# apu-csk-motherboard.net
KiCad netlist of a schematic drawn in EAGLE
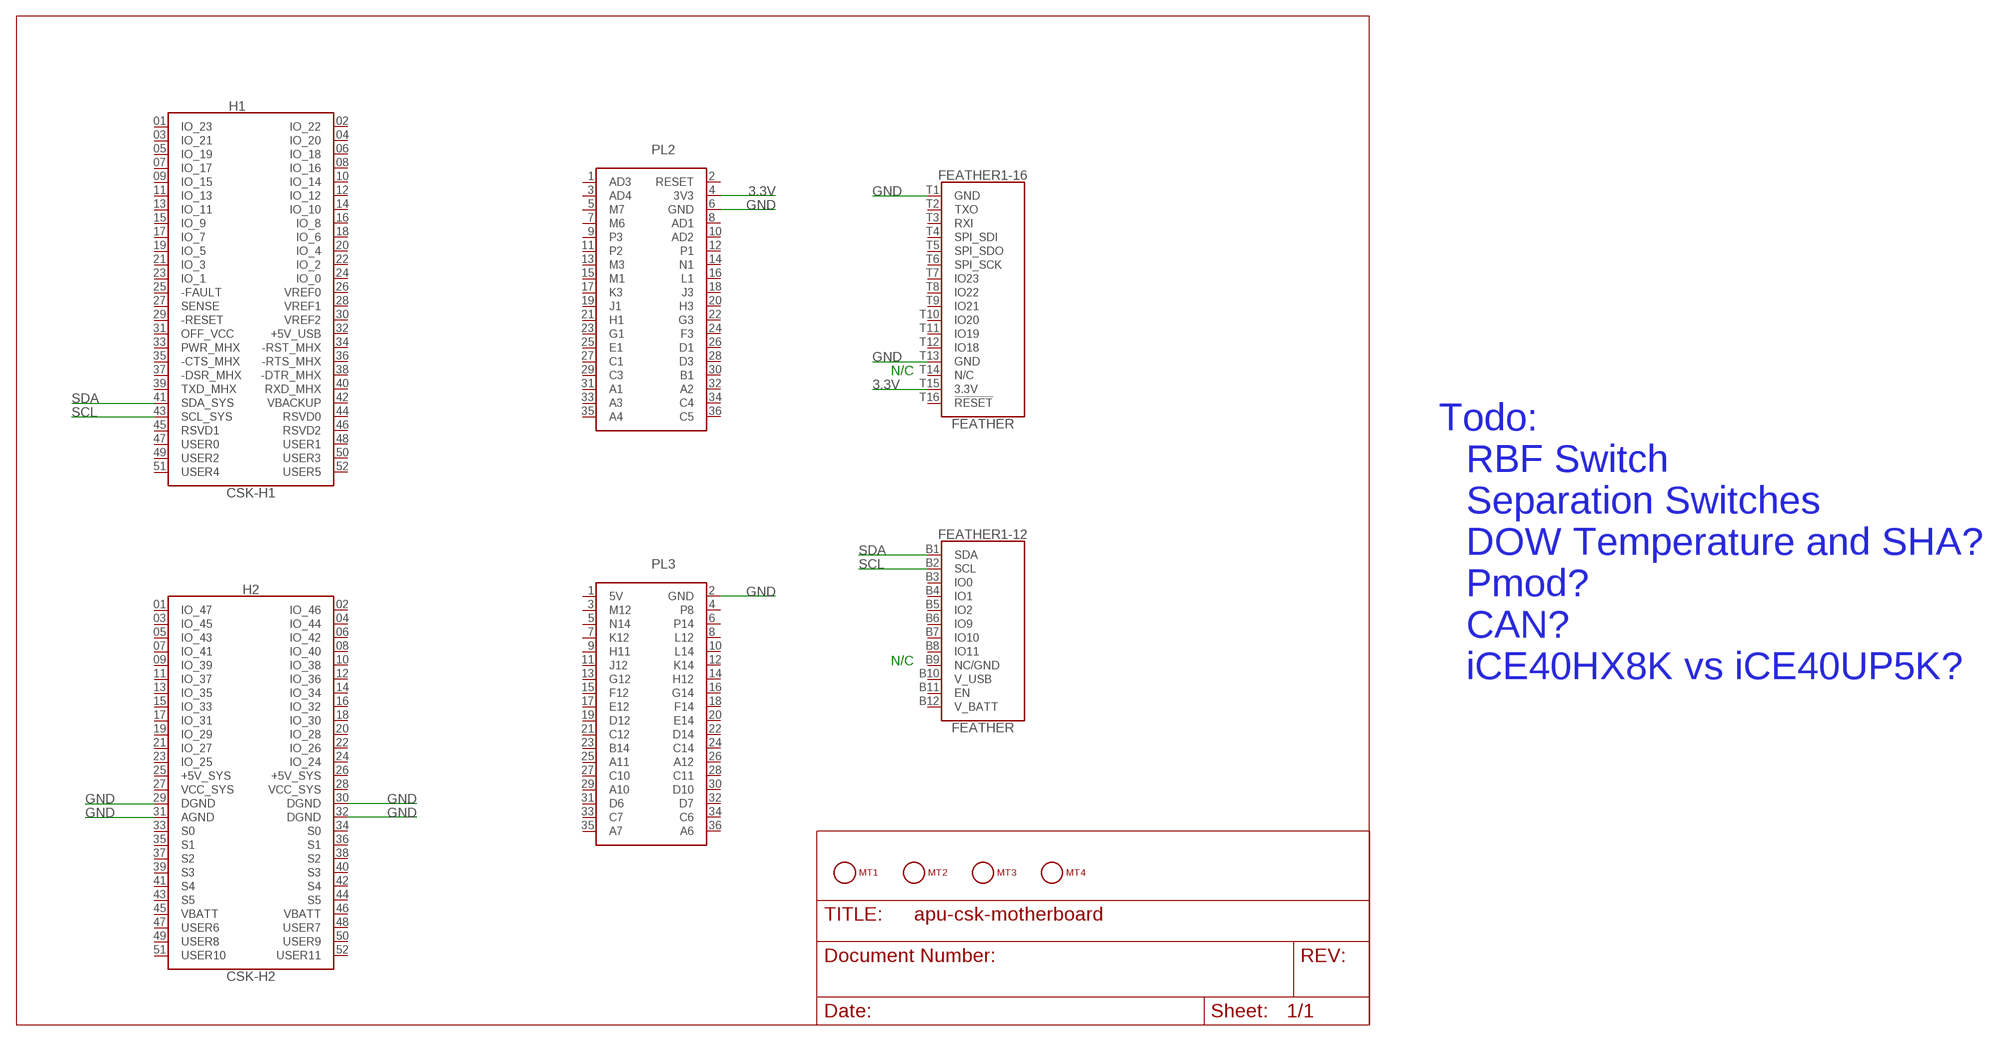
[diagram p0: schematic, sheet 1]

(export (version "E")
  (design (tool "Eeschema 10.0.6"))
  (components
    (comp (ref "FEATHER1")
      (value "FEATHER")
      (footprint "eagle-import:FEATHER")
      (libsource (lib "eagle-import") (part "FEATHER"))
    )
    (comp (ref "H1")
      (value "CSK-H1")
      (footprint "eagle-import:SAMTEC_ESQ-126-37-G-D--NUMBERED-FOR-CUBESAT-BUS")
      (libsource (lib "eagle-import") (part "CSK-H1"))
    )
    (comp (ref "H2")
      (value "CSK-H2")
      (footprint "eagle-import:SAMTEC_ESQ-126-37-G-D--NUMBERED-FOR-CUBESAT-BUS")
      (libsource (lib "eagle-import") (part "CSK-H2"))
    )
    (comp (ref "MT1")
      (value "MOUNTING_HOLE-125_250_ROUND")
      (footprint "eagle-import:MT_125_250")
      (libsource (lib "eagle-import") (part "MOUNTING_HOLE-125_250_ROUND"))
    )
    (comp (ref "MT2")
      (value "MOUNTING_HOLE-125_250_ROUND")
      (footprint "eagle-import:MT_125_250")
      (libsource (lib "eagle-import") (part "MOUNTING_HOLE-125_250_ROUND"))
    )
    (comp (ref "MT3")
      (value "MOUNTING_HOLE-125_250_ROUND")
      (footprint "eagle-import:MT_125_250")
      (libsource (lib "eagle-import") (part "MOUNTING_HOLE-125_250_ROUND"))
    )
    (comp (ref "MT4")
      (value "MOUNTING_HOLE-125_250_ROUND")
      (footprint "eagle-import:MT_125_250")
      (libsource (lib "eagle-import") (part "MOUNTING_HOLE-125_250_ROUND"))
    )
    (comp (ref "PL2")
      (value "ICEWERX-PL2")
      (footprint "eagle-import:TE_4-1734506-1")
      (libsource (lib "eagle-import") (part "ICEWERX-PL2"))
    )
    (comp (ref "PL3")
      (value "ICEWERX-PL3")
      (footprint "eagle-import:TE_4-1734506-1")
      (libsource (lib "eagle-import") (part "ICEWERX-PL3"))
    )
  )
  (nets
    (net (code "1") (name "/3.3V") (class "Default")
      (node (ref "FEATHER1") (pin "T15") (pinfunction "3.3V_T15") (pintype "bidirectional"))
      (node (ref "PL2") (pin "4") (pinfunction "3V3_4") (pintype "bidirectional"))
    )
    (net (code "2") (name "/GND") (class "Default")
      (node (ref "FEATHER1") (pin "T1") (pinfunction "GND_T1") (pintype "bidirectional"))
      (node (ref "FEATHER1") (pin "T13") (pinfunction "GND_T13") (pintype "bidirectional"))
      (node (ref "H2") (pin "29") (pinfunction "DGND_29") (pintype "bidirectional"))
      (node (ref "H2") (pin "30") (pinfunction "DGND_30") (pintype "bidirectional"))
      (node (ref "H2") (pin "31") (pinfunction "AGND_31") (pintype "bidirectional"))
      (node (ref "H2") (pin "32") (pinfunction "DGND_32") (pintype "bidirectional"))
      (node (ref "PL2") (pin "6") (pinfunction "GND_6") (pintype "bidirectional"))
      (node (ref "PL3") (pin "2") (pinfunction "GND_2") (pintype "bidirectional"))
    )
    (net (code "3") (name "/SCL") (class "Default")
      (node (ref "FEATHER1") (pin "B2") (pinfunction "SCL_B2") (pintype "bidirectional"))
      (node (ref "H1") (pin "43") (pinfunction "SCL_SYS_43") (pintype "bidirectional"))
    )
    (net (code "4") (name "/SDA") (class "Default")
      (node (ref "FEATHER1") (pin "B1") (pinfunction "SDA_B1") (pintype "bidirectional"))
      (node (ref "H1") (pin "41") (pinfunction "SDA_SYS_41") (pintype "bidirectional"))
    )
    (net (code "5") (name "unconnected-(FEATHER1A-EN-PadB11)") (class "Default")
      (node (ref "FEATHER1") (pin "B11") (pinfunction "EN_B11") (pintype "bidirectional"))
    )
    (net (code "6") (name "unconnected-(FEATHER1A-IO0-PadB3)") (class "Default")
      (node (ref "FEATHER1") (pin "B3") (pinfunction "IO0_B3") (pintype "bidirectional"))
    )
    (net (code "7") (name "unconnected-(FEATHER1A-IO1-PadB4)") (class "Default")
      (node (ref "FEATHER1") (pin "B4") (pinfunction "IO1_B4") (pintype "bidirectional"))
    )
    (net (code "8") (name "unconnected-(FEATHER1A-IO2-PadB5)") (class "Default")
      (node (ref "FEATHER1") (pin "B5") (pinfunction "IO2_B5") (pintype "bidirectional"))
    )
    (net (code "9") (name "unconnected-(FEATHER1A-IO9-PadB6)") (class "Default")
      (node (ref "FEATHER1") (pin "B6") (pinfunction "IO9_B6") (pintype "bidirectional"))
    )
    (net (code "10") (name "unconnected-(FEATHER1A-IO10-PadB7)") (class "Default")
      (node (ref "FEATHER1") (pin "B7") (pinfunction "IO10_B7") (pintype "bidirectional"))
    )
    (net (code "11") (name "unconnected-(FEATHER1A-IO11-PadB8)") (class "Default")
      (node (ref "FEATHER1") (pin "B8") (pinfunction "IO11_B8") (pintype "bidirectional"))
    )
    (net (code "12") (name "unconnected-(FEATHER1A-NC{slash}GND-PadB9)") (class "Default")
      (node (ref "FEATHER1") (pin "B9") (pinfunction "NC/GND_B9") (pintype "bidirectional"))
    )
    (net (code "13") (name "unconnected-(FEATHER1A-V_BATT-PadB12)") (class "Default")
      (node (ref "FEATHER1") (pin "B12") (pinfunction "V_BATT_B12") (pintype "bidirectional"))
    )
    (net (code "14") (name "unconnected-(FEATHER1A-V_USB-PadB10)") (class "Default")
      (node (ref "FEATHER1") (pin "B10") (pinfunction "V_USB_B10") (pintype "bidirectional"))
    )
    (net (code "15") (name "unconnected-(FEATHER1B-IO18-PadT12)") (class "Default")
      (node (ref "FEATHER1") (pin "T12") (pinfunction "IO18_T12") (pintype "bidirectional"))
    )
    (net (code "16") (name "unconnected-(FEATHER1B-IO19-PadT11)") (class "Default")
      (node (ref "FEATHER1") (pin "T11") (pinfunction "IO19_T11") (pintype "bidirectional"))
    )
    (net (code "17") (name "unconnected-(FEATHER1B-IO20-PadT10)") (class "Default")
      (node (ref "FEATHER1") (pin "T10") (pinfunction "IO20_T10") (pintype "bidirectional"))
    )
    (net (code "18") (name "unconnected-(FEATHER1B-IO21-PadT9)") (class "Default")
      (node (ref "FEATHER1") (pin "T9") (pinfunction "IO21_T9") (pintype "bidirectional"))
    )
    (net (code "19") (name "unconnected-(FEATHER1B-IO22-PadT8)") (class "Default")
      (node (ref "FEATHER1") (pin "T8") (pinfunction "IO22_T8") (pintype "bidirectional"))
    )
    (net (code "20") (name "unconnected-(FEATHER1B-IO23-PadT7)") (class "Default")
      (node (ref "FEATHER1") (pin "T7") (pinfunction "IO23_T7") (pintype "bidirectional"))
    )
    (net (code "21") (name "unconnected-(FEATHER1B-N{slash}C-PadT14)") (class "Default")
      (node (ref "FEATHER1") (pin "T14") (pinfunction "N/C_T14") (pintype "bidirectional"))
    )
    (net (code "22") (name "unconnected-(FEATHER1B-RXI-PadT3)") (class "Default")
      (node (ref "FEATHER1") (pin "T3") (pinfunction "RXI_T3") (pintype "bidirectional"))
    )
    (net (code "23") (name "unconnected-(FEATHER1B-SPI_SCK-PadT6)") (class "Default")
      (node (ref "FEATHER1") (pin "T6") (pinfunction "SPI_SCK_T6") (pintype "bidirectional"))
    )
    (net (code "24") (name "unconnected-(FEATHER1B-SPI_SDI-PadT4)") (class "Default")
      (node (ref "FEATHER1") (pin "T4") (pinfunction "SPI_SDI_T4") (pintype "bidirectional"))
    )
    (net (code "25") (name "unconnected-(FEATHER1B-SPI_SDO-PadT5)") (class "Default")
      (node (ref "FEATHER1") (pin "T5") (pinfunction "SPI_SDO_T5") (pintype "bidirectional"))
    )
    (net (code "26") (name "unconnected-(FEATHER1B-TXO-PadT2)") (class "Default")
      (node (ref "FEATHER1") (pin "T2") (pinfunction "TXO_T2") (pintype "bidirectional"))
    )
    (net (code "27") (name "unconnected-(FEATHER1B-~{RESET}-PadT16)") (class "Default")
      (node (ref "FEATHER1") (pin "T16") (pinfunction "~{RESET}_T16") (pintype "bidirectional"))
    )
    (net (code "28") (name "unconnected-(H1-+5V_USB-Pad32)") (class "Default")
      (node (ref "H1") (pin "32") (pinfunction "+5V_USB_32") (pintype "bidirectional"))
    )
    (net (code "29") (name "unconnected-(H1--CTS_MHX-Pad35)") (class "Default")
      (node (ref "H1") (pin "35") (pinfunction "-CTS_MHX_35") (pintype "bidirectional"))
    )
    (net (code "30") (name "unconnected-(H1--DSR_MHX-Pad37)") (class "Default")
      (node (ref "H1") (pin "37") (pinfunction "-DSR_MHX_37") (pintype "bidirectional"))
    )
    (net (code "31") (name "unconnected-(H1--DTR_MHX-Pad38)") (class "Default")
      (node (ref "H1") (pin "38") (pinfunction "-DTR_MHX_38") (pintype "bidirectional"))
    )
    (net (code "32") (name "unconnected-(H1--FAULT-Pad25)") (class "Default")
      (node (ref "H1") (pin "25") (pinfunction "-FAULT_25") (pintype "bidirectional"))
    )
    (net (code "33") (name "unconnected-(H1--RESET-Pad29)") (class "Default")
      (node (ref "H1") (pin "29") (pinfunction "-RESET_29") (pintype "bidirectional"))
    )
    (net (code "34") (name "unconnected-(H1--RST_MHX-Pad34)") (class "Default")
      (node (ref "H1") (pin "34") (pinfunction "-RST_MHX_34") (pintype "bidirectional"))
    )
    (net (code "35") (name "unconnected-(H1--RTS_MHX-Pad36)") (class "Default")
      (node (ref "H1") (pin "36") (pinfunction "-RTS_MHX_36") (pintype "bidirectional"))
    )
    (net (code "36") (name "unconnected-(H1-IO_0-Pad24)") (class "Default")
      (node (ref "H1") (pin "24") (pinfunction "IO_0_24") (pintype "bidirectional"))
    )
    (net (code "37") (name "unconnected-(H1-IO_1-Pad23)") (class "Default")
      (node (ref "H1") (pin "23") (pinfunction "IO_1_23") (pintype "bidirectional"))
    )
    (net (code "38") (name "unconnected-(H1-IO_2-Pad22)") (class "Default")
      (node (ref "H1") (pin "22") (pinfunction "IO_2_22") (pintype "bidirectional"))
    )
    (net (code "39") (name "unconnected-(H1-IO_3-Pad21)") (class "Default")
      (node (ref "H1") (pin "21") (pinfunction "IO_3_21") (pintype "bidirectional"))
    )
    (net (code "40") (name "unconnected-(H1-IO_4-Pad20)") (class "Default")
      (node (ref "H1") (pin "20") (pinfunction "IO_4_20") (pintype "bidirectional"))
    )
    (net (code "41") (name "unconnected-(H1-IO_5-Pad19)") (class "Default")
      (node (ref "H1") (pin "19") (pinfunction "IO_5_19") (pintype "bidirectional"))
    )
    (net (code "42") (name "unconnected-(H1-IO_6-Pad18)") (class "Default")
      (node (ref "H1") (pin "18") (pinfunction "IO_6_18") (pintype "bidirectional"))
    )
    (net (code "43") (name "unconnected-(H1-IO_7-Pad17)") (class "Default")
      (node (ref "H1") (pin "17") (pinfunction "IO_7_17") (pintype "bidirectional"))
    )
    (net (code "44") (name "unconnected-(H1-IO_8-Pad16)") (class "Default")
      (node (ref "H1") (pin "16") (pinfunction "IO_8_16") (pintype "bidirectional"))
    )
    (net (code "45") (name "unconnected-(H1-IO_9-Pad15)") (class "Default")
      (node (ref "H1") (pin "15") (pinfunction "IO_9_15") (pintype "bidirectional"))
    )
    (net (code "46") (name "unconnected-(H1-IO_10-Pad14)") (class "Default")
      (node (ref "H1") (pin "14") (pinfunction "IO_10_14") (pintype "bidirectional"))
    )
    (net (code "47") (name "unconnected-(H1-IO_11-Pad13)") (class "Default")
      (node (ref "H1") (pin "13") (pinfunction "IO_11_13") (pintype "bidirectional"))
    )
    (net (code "48") (name "unconnected-(H1-IO_12-Pad12)") (class "Default")
      (node (ref "H1") (pin "12") (pinfunction "IO_12_12") (pintype "bidirectional"))
    )
    (net (code "49") (name "unconnected-(H1-IO_13-Pad11)") (class "Default")
      (node (ref "H1") (pin "11") (pinfunction "IO_13_11") (pintype "bidirectional"))
    )
    (net (code "50") (name "unconnected-(H1-IO_14-Pad10)") (class "Default")
      (node (ref "H1") (pin "10") (pinfunction "IO_14_10") (pintype "bidirectional"))
    )
    (net (code "51") (name "unconnected-(H1-IO_15-Pad09)") (class "Default")
      (node (ref "H1") (pin "09") (pinfunction "IO_15_09") (pintype "bidirectional"))
    )
    (net (code "52") (name "unconnected-(H1-IO_16-Pad08)") (class "Default")
      (node (ref "H1") (pin "08") (pinfunction "IO_16_08") (pintype "bidirectional"))
    )
    (net (code "53") (name "unconnected-(H1-IO_17-Pad07)") (class "Default")
      (node (ref "H1") (pin "07") (pinfunction "IO_17_07") (pintype "bidirectional"))
    )
    (net (code "54") (name "unconnected-(H1-IO_18-Pad06)") (class "Default")
      (node (ref "H1") (pin "06") (pinfunction "IO_18_06") (pintype "bidirectional"))
    )
    (net (code "55") (name "unconnected-(H1-IO_19-Pad05)") (class "Default")
      (node (ref "H1") (pin "05") (pinfunction "IO_19_05") (pintype "bidirectional"))
    )
    (net (code "56") (name "unconnected-(H1-IO_20-Pad04)") (class "Default")
      (node (ref "H1") (pin "04") (pinfunction "IO_20_04") (pintype "bidirectional"))
    )
    (net (code "57") (name "unconnected-(H1-IO_21-Pad03)") (class "Default")
      (node (ref "H1") (pin "03") (pinfunction "IO_21_03") (pintype "bidirectional"))
    )
    (net (code "58") (name "unconnected-(H1-IO_22-Pad02)") (class "Default")
      (node (ref "H1") (pin "02") (pinfunction "IO_22_02") (pintype "bidirectional"))
    )
    (net (code "59") (name "unconnected-(H1-IO_23-Pad01)") (class "Default")
      (node (ref "H1") (pin "01") (pinfunction "IO_23_01") (pintype "bidirectional"))
    )
    (net (code "60") (name "unconnected-(H1-OFF_VCC-Pad31)") (class "Default")
      (node (ref "H1") (pin "31") (pinfunction "OFF_VCC_31") (pintype "bidirectional"))
    )
    (net (code "61") (name "unconnected-(H1-PWR_MHX-Pad33)") (class "Default")
      (node (ref "H1") (pin "33") (pinfunction "PWR_MHX_33") (pintype "bidirectional"))
    )
    (net (code "62") (name "unconnected-(H1-RSVD0-Pad44)") (class "Default")
      (node (ref "H1") (pin "44") (pinfunction "RSVD0_44") (pintype "bidirectional"))
    )
    (net (code "63") (name "unconnected-(H1-RSVD1-Pad45)") (class "Default")
      (node (ref "H1") (pin "45") (pinfunction "RSVD1_45") (pintype "bidirectional"))
    )
    (net (code "64") (name "unconnected-(H1-RSVD2-Pad46)") (class "Default")
      (node (ref "H1") (pin "46") (pinfunction "RSVD2_46") (pintype "bidirectional"))
    )
    (net (code "65") (name "unconnected-(H1-RXD_MHX-Pad40)") (class "Default")
      (node (ref "H1") (pin "40") (pinfunction "RXD_MHX_40") (pintype "bidirectional"))
    )
    (net (code "66") (name "unconnected-(H1-SENSE-Pad27)") (class "Default")
      (node (ref "H1") (pin "27") (pinfunction "SENSE_27") (pintype "bidirectional"))
    )
    (net (code "67") (name "unconnected-(H1-TXD_MHX-Pad39)") (class "Default")
      (node (ref "H1") (pin "39") (pinfunction "TXD_MHX_39") (pintype "bidirectional"))
    )
    (net (code "68") (name "unconnected-(H1-USER0-Pad47)") (class "Default")
      (node (ref "H1") (pin "47") (pinfunction "USER0_47") (pintype "bidirectional"))
    )
    (net (code "69") (name "unconnected-(H1-USER1-Pad48)") (class "Default")
      (node (ref "H1") (pin "48") (pinfunction "USER1_48") (pintype "bidirectional"))
    )
    (net (code "70") (name "unconnected-(H1-USER2-Pad49)") (class "Default")
      (node (ref "H1") (pin "49") (pinfunction "USER2_49") (pintype "bidirectional"))
    )
    (net (code "71") (name "unconnected-(H1-USER3-Pad50)") (class "Default")
      (node (ref "H1") (pin "50") (pinfunction "USER3_50") (pintype "bidirectional"))
    )
    (net (code "72") (name "unconnected-(H1-USER4-Pad51)") (class "Default")
      (node (ref "H1") (pin "51") (pinfunction "USER4_51") (pintype "bidirectional"))
    )
    (net (code "73") (name "unconnected-(H1-USER5-Pad52)") (class "Default")
      (node (ref "H1") (pin "52") (pinfunction "USER5_52") (pintype "bidirectional"))
    )
    (net (code "74") (name "unconnected-(H1-VBACKUP-Pad42)") (class "Default")
      (node (ref "H1") (pin "42") (pinfunction "VBACKUP_42") (pintype "bidirectional"))
    )
    (net (code "75") (name "unconnected-(H1-VREF0-Pad26)") (class "Default")
      (node (ref "H1") (pin "26") (pinfunction "VREF0_26") (pintype "bidirectional"))
    )
    (net (code "76") (name "unconnected-(H1-VREF1-Pad28)") (class "Default")
      (node (ref "H1") (pin "28") (pinfunction "VREF1_28") (pintype "bidirectional"))
    )
    (net (code "77") (name "unconnected-(H1-VREF2-Pad30)") (class "Default")
      (node (ref "H1") (pin "30") (pinfunction "VREF2_30") (pintype "bidirectional"))
    )
    (net (code "78") (name "unconnected-(H2-+5V_SYS-Pad25)") (class "Default")
      (node (ref "H2") (pin "25") (pinfunction "+5V_SYS_25") (pintype "bidirectional"))
    )
    (net (code "79") (name "unconnected-(H2-+5V_SYS-Pad26)") (class "Default")
      (node (ref "H2") (pin "26") (pinfunction "+5V_SYS_26") (pintype "bidirectional"))
    )
    (net (code "80") (name "unconnected-(H2-IO_24-Pad24)") (class "Default")
      (node (ref "H2") (pin "24") (pinfunction "IO_24_24") (pintype "bidirectional"))
    )
    (net (code "81") (name "unconnected-(H2-IO_25-Pad23)") (class "Default")
      (node (ref "H2") (pin "23") (pinfunction "IO_25_23") (pintype "bidirectional"))
    )
    (net (code "82") (name "unconnected-(H2-IO_26-Pad22)") (class "Default")
      (node (ref "H2") (pin "22") (pinfunction "IO_26_22") (pintype "bidirectional"))
    )
    (net (code "83") (name "unconnected-(H2-IO_27-Pad21)") (class "Default")
      (node (ref "H2") (pin "21") (pinfunction "IO_27_21") (pintype "bidirectional"))
    )
    (net (code "84") (name "unconnected-(H2-IO_28-Pad20)") (class "Default")
      (node (ref "H2") (pin "20") (pinfunction "IO_28_20") (pintype "bidirectional"))
    )
    (net (code "85") (name "unconnected-(H2-IO_29-Pad19)") (class "Default")
      (node (ref "H2") (pin "19") (pinfunction "IO_29_19") (pintype "bidirectional"))
    )
    (net (code "86") (name "unconnected-(H2-IO_30-Pad18)") (class "Default")
      (node (ref "H2") (pin "18") (pinfunction "IO_30_18") (pintype "bidirectional"))
    )
    (net (code "87") (name "unconnected-(H2-IO_31-Pad17)") (class "Default")
      (node (ref "H2") (pin "17") (pinfunction "IO_31_17") (pintype "bidirectional"))
    )
    (net (code "88") (name "unconnected-(H2-IO_32-Pad16)") (class "Default")
      (node (ref "H2") (pin "16") (pinfunction "IO_32_16") (pintype "bidirectional"))
    )
    (net (code "89") (name "unconnected-(H2-IO_33-Pad15)") (class "Default")
      (node (ref "H2") (pin "15") (pinfunction "IO_33_15") (pintype "bidirectional"))
    )
    (net (code "90") (name "unconnected-(H2-IO_34-Pad14)") (class "Default")
      (node (ref "H2") (pin "14") (pinfunction "IO_34_14") (pintype "bidirectional"))
    )
    (net (code "91") (name "unconnected-(H2-IO_35-Pad13)") (class "Default")
      (node (ref "H2") (pin "13") (pinfunction "IO_35_13") (pintype "bidirectional"))
    )
    (net (code "92") (name "unconnected-(H2-IO_36-Pad12)") (class "Default")
      (node (ref "H2") (pin "12") (pinfunction "IO_36_12") (pintype "bidirectional"))
    )
    (net (code "93") (name "unconnected-(H2-IO_37-Pad11)") (class "Default")
      (node (ref "H2") (pin "11") (pinfunction "IO_37_11") (pintype "bidirectional"))
    )
    (net (code "94") (name "unconnected-(H2-IO_38-Pad10)") (class "Default")
      (node (ref "H2") (pin "10") (pinfunction "IO_38_10") (pintype "bidirectional"))
    )
    (net (code "95") (name "unconnected-(H2-IO_39-Pad09)") (class "Default")
      (node (ref "H2") (pin "09") (pinfunction "IO_39_09") (pintype "bidirectional"))
    )
    (net (code "96") (name "unconnected-(H2-IO_40-Pad08)") (class "Default")
      (node (ref "H2") (pin "08") (pinfunction "IO_40_08") (pintype "bidirectional"))
    )
    (net (code "97") (name "unconnected-(H2-IO_41-Pad07)") (class "Default")
      (node (ref "H2") (pin "07") (pinfunction "IO_41_07") (pintype "bidirectional"))
    )
    (net (code "98") (name "unconnected-(H2-IO_42-Pad06)") (class "Default")
      (node (ref "H2") (pin "06") (pinfunction "IO_42_06") (pintype "bidirectional"))
    )
    (net (code "99") (name "unconnected-(H2-IO_43-Pad05)") (class "Default")
      (node (ref "H2") (pin "05") (pinfunction "IO_43_05") (pintype "bidirectional"))
    )
    (net (code "100") (name "unconnected-(H2-IO_44-Pad04)") (class "Default")
      (node (ref "H2") (pin "04") (pinfunction "IO_44_04") (pintype "bidirectional"))
    )
    (net (code "101") (name "unconnected-(H2-IO_45-Pad03)") (class "Default")
      (node (ref "H2") (pin "03") (pinfunction "IO_45_03") (pintype "bidirectional"))
    )
    (net (code "102") (name "unconnected-(H2-IO_46-Pad02)") (class "Default")
      (node (ref "H2") (pin "02") (pinfunction "IO_46_02") (pintype "bidirectional"))
    )
    (net (code "103") (name "unconnected-(H2-IO_47-Pad01)") (class "Default")
      (node (ref "H2") (pin "01") (pinfunction "IO_47_01") (pintype "bidirectional"))
    )
    (net (code "104") (name "unconnected-(H2-S0-Pad33)") (class "Default")
      (node (ref "H2") (pin "33") (pinfunction "S0_33") (pintype "bidirectional"))
    )
    (net (code "105") (name "unconnected-(H2-S0-Pad34)") (class "Default")
      (node (ref "H2") (pin "34") (pinfunction "S0_34") (pintype "bidirectional"))
    )
    (net (code "106") (name "unconnected-(H2-S1-Pad35)") (class "Default")
      (node (ref "H2") (pin "35") (pinfunction "S1_35") (pintype "bidirectional"))
    )
    (net (code "107") (name "unconnected-(H2-S1-Pad36)") (class "Default")
      (node (ref "H2") (pin "36") (pinfunction "S1_36") (pintype "bidirectional"))
    )
    (net (code "108") (name "unconnected-(H2-S2-Pad37)") (class "Default")
      (node (ref "H2") (pin "37") (pinfunction "S2_37") (pintype "bidirectional"))
    )
    (net (code "109") (name "unconnected-(H2-S2-Pad38)") (class "Default")
      (node (ref "H2") (pin "38") (pinfunction "S2_38") (pintype "bidirectional"))
    )
    (net (code "110") (name "unconnected-(H2-S3-Pad39)") (class "Default")
      (node (ref "H2") (pin "39") (pinfunction "S3_39") (pintype "bidirectional"))
    )
    (net (code "111") (name "unconnected-(H2-S3-Pad40)") (class "Default")
      (node (ref "H2") (pin "40") (pinfunction "S3_40") (pintype "bidirectional"))
    )
    (net (code "112") (name "unconnected-(H2-S4-Pad41)") (class "Default")
      (node (ref "H2") (pin "41") (pinfunction "S4_41") (pintype "bidirectional"))
    )
    (net (code "113") (name "unconnected-(H2-S4-Pad42)") (class "Default")
      (node (ref "H2") (pin "42") (pinfunction "S4_42") (pintype "bidirectional"))
    )
    (net (code "114") (name "unconnected-(H2-S5-Pad43)") (class "Default")
      (node (ref "H2") (pin "43") (pinfunction "S5_43") (pintype "bidirectional"))
    )
    (net (code "115") (name "unconnected-(H2-S5-Pad44)") (class "Default")
      (node (ref "H2") (pin "44") (pinfunction "S5_44") (pintype "bidirectional"))
    )
    (net (code "116") (name "unconnected-(H2-USER6-Pad47)") (class "Default")
      (node (ref "H2") (pin "47") (pinfunction "USER6_47") (pintype "bidirectional"))
    )
    (net (code "117") (name "unconnected-(H2-USER7-Pad48)") (class "Default")
      (node (ref "H2") (pin "48") (pinfunction "USER7_48") (pintype "bidirectional"))
    )
    (net (code "118") (name "unconnected-(H2-USER8-Pad49)") (class "Default")
      (node (ref "H2") (pin "49") (pinfunction "USER8_49") (pintype "bidirectional"))
    )
    (net (code "119") (name "unconnected-(H2-USER9-Pad50)") (class "Default")
      (node (ref "H2") (pin "50") (pinfunction "USER9_50") (pintype "bidirectional"))
    )
    (net (code "120") (name "unconnected-(H2-USER10-Pad51)") (class "Default")
      (node (ref "H2") (pin "51") (pinfunction "USER10_51") (pintype "bidirectional"))
    )
    (net (code "121") (name "unconnected-(H2-USER11-Pad52)") (class "Default")
      (node (ref "H2") (pin "52") (pinfunction "USER11_52") (pintype "bidirectional"))
    )
    (net (code "122") (name "unconnected-(H2-VBATT-Pad45)") (class "Default")
      (node (ref "H2") (pin "45") (pinfunction "VBATT_45") (pintype "bidirectional"))
    )
    (net (code "123") (name "unconnected-(H2-VBATT-Pad46)") (class "Default")
      (node (ref "H2") (pin "46") (pinfunction "VBATT_46") (pintype "bidirectional"))
    )
    (net (code "124") (name "unconnected-(H2-VCC_SYS-Pad27)") (class "Default")
      (node (ref "H2") (pin "27") (pinfunction "VCC_SYS_27") (pintype "bidirectional"))
    )
    (net (code "125") (name "unconnected-(H2-VCC_SYS-Pad28)") (class "Default")
      (node (ref "H2") (pin "28") (pinfunction "VCC_SYS_28") (pintype "bidirectional"))
    )
    (net (code "126") (name "unconnected-(MT1-P$1-Pad1)") (class "Default")
      (node (ref "MT1") (pin "1") (pinfunction "P$1_1") (pintype "bidirectional"))
    )
    (net (code "127") (name "unconnected-(MT2-P$1-Pad1)") (class "Default")
      (node (ref "MT2") (pin "1") (pinfunction "P$1_1") (pintype "bidirectional"))
    )
    (net (code "128") (name "unconnected-(MT3-P$1-Pad1)") (class "Default")
      (node (ref "MT3") (pin "1") (pinfunction "P$1_1") (pintype "bidirectional"))
    )
    (net (code "129") (name "unconnected-(MT4-P$1-Pad1)") (class "Default")
      (node (ref "MT4") (pin "1") (pinfunction "P$1_1") (pintype "bidirectional"))
    )
    (net (code "130") (name "unconnected-(PL2-A1-Pad31)") (class "Default")
      (node (ref "PL2") (pin "31") (pinfunction "A1_31") (pintype "bidirectional"))
    )
    (net (code "131") (name "unconnected-(PL2-A2-Pad32)") (class "Default")
      (node (ref "PL2") (pin "32") (pinfunction "A2_32") (pintype "bidirectional"))
    )
    (net (code "132") (name "unconnected-(PL2-A3-Pad33)") (class "Default")
      (node (ref "PL2") (pin "33") (pinfunction "A3_33") (pintype "bidirectional"))
    )
    (net (code "133") (name "unconnected-(PL2-A4-Pad35)") (class "Default")
      (node (ref "PL2") (pin "35") (pinfunction "A4_35") (pintype "bidirectional"))
    )
    (net (code "134") (name "unconnected-(PL2-AD1-Pad8)") (class "Default")
      (node (ref "PL2") (pin "8") (pinfunction "AD1_8") (pintype "bidirectional"))
    )
    (net (code "135") (name "unconnected-(PL2-AD2-Pad10)") (class "Default")
      (node (ref "PL2") (pin "10") (pinfunction "AD2_10") (pintype "bidirectional"))
    )
    (net (code "136") (name "unconnected-(PL2-AD3-Pad1)") (class "Default")
      (node (ref "PL2") (pin "1") (pinfunction "AD3_1") (pintype "bidirectional"))
    )
    (net (code "137") (name "unconnected-(PL2-AD4-Pad3)") (class "Default")
      (node (ref "PL2") (pin "3") (pinfunction "AD4_3") (pintype "bidirectional"))
    )
    (net (code "138") (name "unconnected-(PL2-B1-Pad30)") (class "Default")
      (node (ref "PL2") (pin "30") (pinfunction "B1_30") (pintype "bidirectional"))
    )
    (net (code "139") (name "unconnected-(PL2-C1-Pad27)") (class "Default")
      (node (ref "PL2") (pin "27") (pinfunction "C1_27") (pintype "bidirectional"))
    )
    (net (code "140") (name "unconnected-(PL2-C3-Pad29)") (class "Default")
      (node (ref "PL2") (pin "29") (pinfunction "C3_29") (pintype "bidirectional"))
    )
    (net (code "141") (name "unconnected-(PL2-C4-Pad34)") (class "Default")
      (node (ref "PL2") (pin "34") (pinfunction "C4_34") (pintype "bidirectional"))
    )
    (net (code "142") (name "unconnected-(PL2-C5-Pad36)") (class "Default")
      (node (ref "PL2") (pin "36") (pinfunction "C5_36") (pintype "bidirectional"))
    )
    (net (code "143") (name "unconnected-(PL2-D1-Pad26)") (class "Default")
      (node (ref "PL2") (pin "26") (pinfunction "D1_26") (pintype "bidirectional"))
    )
    (net (code "144") (name "unconnected-(PL2-D3-Pad28)") (class "Default")
      (node (ref "PL2") (pin "28") (pinfunction "D3_28") (pintype "bidirectional"))
    )
    (net (code "145") (name "unconnected-(PL2-E1-Pad25)") (class "Default")
      (node (ref "PL2") (pin "25") (pinfunction "E1_25") (pintype "bidirectional"))
    )
    (net (code "146") (name "unconnected-(PL2-F3-Pad24)") (class "Default")
      (node (ref "PL2") (pin "24") (pinfunction "F3_24") (pintype "bidirectional"))
    )
    (net (code "147") (name "unconnected-(PL2-G1-Pad23)") (class "Default")
      (node (ref "PL2") (pin "23") (pinfunction "G1_23") (pintype "bidirectional"))
    )
    (net (code "148") (name "unconnected-(PL2-G3-Pad22)") (class "Default")
      (node (ref "PL2") (pin "22") (pinfunction "G3_22") (pintype "bidirectional"))
    )
    (net (code "149") (name "unconnected-(PL2-H1-Pad21)") (class "Default")
      (node (ref "PL2") (pin "21") (pinfunction "H1_21") (pintype "bidirectional"))
    )
    (net (code "150") (name "unconnected-(PL2-H3-Pad20)") (class "Default")
      (node (ref "PL2") (pin "20") (pinfunction "H3_20") (pintype "bidirectional"))
    )
    (net (code "151") (name "unconnected-(PL2-J1-Pad19)") (class "Default")
      (node (ref "PL2") (pin "19") (pinfunction "J1_19") (pintype "bidirectional"))
    )
    (net (code "152") (name "unconnected-(PL2-J3-Pad18)") (class "Default")
      (node (ref "PL2") (pin "18") (pinfunction "J3_18") (pintype "bidirectional"))
    )
    (net (code "153") (name "unconnected-(PL2-K3-Pad17)") (class "Default")
      (node (ref "PL2") (pin "17") (pinfunction "K3_17") (pintype "bidirectional"))
    )
    (net (code "154") (name "unconnected-(PL2-L1-Pad16)") (class "Default")
      (node (ref "PL2") (pin "16") (pinfunction "L1_16") (pintype "bidirectional"))
    )
    (net (code "155") (name "unconnected-(PL2-M1-Pad15)") (class "Default")
      (node (ref "PL2") (pin "15") (pinfunction "M1_15") (pintype "bidirectional"))
    )
    (net (code "156") (name "unconnected-(PL2-M3-Pad13)") (class "Default")
      (node (ref "PL2") (pin "13") (pinfunction "M3_13") (pintype "bidirectional"))
    )
    (net (code "157") (name "unconnected-(PL2-M6-Pad7)") (class "Default")
      (node (ref "PL2") (pin "7") (pinfunction "M6_7") (pintype "bidirectional"))
    )
    (net (code "158") (name "unconnected-(PL2-M7-Pad5)") (class "Default")
      (node (ref "PL2") (pin "5") (pinfunction "M7_5") (pintype "bidirectional"))
    )
    (net (code "159") (name "unconnected-(PL2-N1-Pad14)") (class "Default")
      (node (ref "PL2") (pin "14") (pinfunction "N1_14") (pintype "bidirectional"))
    )
    (net (code "160") (name "unconnected-(PL2-P1-Pad12)") (class "Default")
      (node (ref "PL2") (pin "12") (pinfunction "P1_12") (pintype "bidirectional"))
    )
    (net (code "161") (name "unconnected-(PL2-P2-Pad11)") (class "Default")
      (node (ref "PL2") (pin "11") (pinfunction "P2_11") (pintype "bidirectional"))
    )
    (net (code "162") (name "unconnected-(PL2-P3-Pad9)") (class "Default")
      (node (ref "PL2") (pin "9") (pinfunction "P3_9") (pintype "bidirectional"))
    )
    (net (code "163") (name "unconnected-(PL2-RESET-Pad2)") (class "Default")
      (node (ref "PL2") (pin "2") (pinfunction "RESET_2") (pintype "bidirectional"))
    )
    (net (code "164") (name "unconnected-(PL3-5V-Pad1)") (class "Default")
      (node (ref "PL3") (pin "1") (pinfunction "5V_1") (pintype "bidirectional"))
    )
    (net (code "165") (name "unconnected-(PL3-A6-Pad36)") (class "Default")
      (node (ref "PL3") (pin "36") (pinfunction "A6_36") (pintype "bidirectional"))
    )
    (net (code "166") (name "unconnected-(PL3-A7-Pad35)") (class "Default")
      (node (ref "PL3") (pin "35") (pinfunction "A7_35") (pintype "bidirectional"))
    )
    (net (code "167") (name "unconnected-(PL3-A10-Pad29)") (class "Default")
      (node (ref "PL3") (pin "29") (pinfunction "A10_29") (pintype "bidirectional"))
    )
    (net (code "168") (name "unconnected-(PL3-A11-Pad25)") (class "Default")
      (node (ref "PL3") (pin "25") (pinfunction "A11_25") (pintype "bidirectional"))
    )
    (net (code "169") (name "unconnected-(PL3-A12-Pad26)") (class "Default")
      (node (ref "PL3") (pin "26") (pinfunction "A12_26") (pintype "bidirectional"))
    )
    (net (code "170") (name "unconnected-(PL3-B14-Pad23)") (class "Default")
      (node (ref "PL3") (pin "23") (pinfunction "B14_23") (pintype "bidirectional"))
    )
    (net (code "171") (name "unconnected-(PL3-C6-Pad34)") (class "Default")
      (node (ref "PL3") (pin "34") (pinfunction "C6_34") (pintype "bidirectional"))
    )
    (net (code "172") (name "unconnected-(PL3-C7-Pad33)") (class "Default")
      (node (ref "PL3") (pin "33") (pinfunction "C7_33") (pintype "bidirectional"))
    )
    (net (code "173") (name "unconnected-(PL3-C10-Pad27)") (class "Default")
      (node (ref "PL3") (pin "27") (pinfunction "C10_27") (pintype "bidirectional"))
    )
    (net (code "174") (name "unconnected-(PL3-C11-Pad28)") (class "Default")
      (node (ref "PL3") (pin "28") (pinfunction "C11_28") (pintype "bidirectional"))
    )
    (net (code "175") (name "unconnected-(PL3-C12-Pad21)") (class "Default")
      (node (ref "PL3") (pin "21") (pinfunction "C12_21") (pintype "bidirectional"))
    )
    (net (code "176") (name "unconnected-(PL3-C14-Pad24)") (class "Default")
      (node (ref "PL3") (pin "24") (pinfunction "C14_24") (pintype "bidirectional"))
    )
    (net (code "177") (name "unconnected-(PL3-D6-Pad31)") (class "Default")
      (node (ref "PL3") (pin "31") (pinfunction "D6_31") (pintype "bidirectional"))
    )
    (net (code "178") (name "unconnected-(PL3-D7-Pad32)") (class "Default")
      (node (ref "PL3") (pin "32") (pinfunction "D7_32") (pintype "bidirectional"))
    )
    (net (code "179") (name "unconnected-(PL3-D10-Pad30)") (class "Default")
      (node (ref "PL3") (pin "30") (pinfunction "D10_30") (pintype "bidirectional"))
    )
    (net (code "180") (name "unconnected-(PL3-D12-Pad19)") (class "Default")
      (node (ref "PL3") (pin "19") (pinfunction "D12_19") (pintype "bidirectional"))
    )
    (net (code "181") (name "unconnected-(PL3-D14-Pad22)") (class "Default")
      (node (ref "PL3") (pin "22") (pinfunction "D14_22") (pintype "bidirectional"))
    )
    (net (code "182") (name "unconnected-(PL3-E12-Pad17)") (class "Default")
      (node (ref "PL3") (pin "17") (pinfunction "E12_17") (pintype "bidirectional"))
    )
    (net (code "183") (name "unconnected-(PL3-E14-Pad20)") (class "Default")
      (node (ref "PL3") (pin "20") (pinfunction "E14_20") (pintype "bidirectional"))
    )
    (net (code "184") (name "unconnected-(PL3-F12-Pad15)") (class "Default")
      (node (ref "PL3") (pin "15") (pinfunction "F12_15") (pintype "bidirectional"))
    )
    (net (code "185") (name "unconnected-(PL3-F14-Pad18)") (class "Default")
      (node (ref "PL3") (pin "18") (pinfunction "F14_18") (pintype "bidirectional"))
    )
    (net (code "186") (name "unconnected-(PL3-G12-Pad13)") (class "Default")
      (node (ref "PL3") (pin "13") (pinfunction "G12_13") (pintype "bidirectional"))
    )
    (net (code "187") (name "unconnected-(PL3-G14-Pad16)") (class "Default")
      (node (ref "PL3") (pin "16") (pinfunction "G14_16") (pintype "bidirectional"))
    )
    (net (code "188") (name "unconnected-(PL3-H11-Pad9)") (class "Default")
      (node (ref "PL3") (pin "9") (pinfunction "H11_9") (pintype "bidirectional"))
    )
    (net (code "189") (name "unconnected-(PL3-H12-Pad14)") (class "Default")
      (node (ref "PL3") (pin "14") (pinfunction "H12_14") (pintype "bidirectional"))
    )
    (net (code "190") (name "unconnected-(PL3-J12-Pad11)") (class "Default")
      (node (ref "PL3") (pin "11") (pinfunction "J12_11") (pintype "bidirectional"))
    )
    (net (code "191") (name "unconnected-(PL3-K12-Pad7)") (class "Default")
      (node (ref "PL3") (pin "7") (pinfunction "K12_7") (pintype "bidirectional"))
    )
    (net (code "192") (name "unconnected-(PL3-K14-Pad12)") (class "Default")
      (node (ref "PL3") (pin "12") (pinfunction "K14_12") (pintype "bidirectional"))
    )
    (net (code "193") (name "unconnected-(PL3-L12-Pad8)") (class "Default")
      (node (ref "PL3") (pin "8") (pinfunction "L12_8") (pintype "bidirectional"))
    )
    (net (code "194") (name "unconnected-(PL3-L14-Pad10)") (class "Default")
      (node (ref "PL3") (pin "10") (pinfunction "L14_10") (pintype "bidirectional"))
    )
    (net (code "195") (name "unconnected-(PL3-M12-Pad3)") (class "Default")
      (node (ref "PL3") (pin "3") (pinfunction "M12_3") (pintype "bidirectional"))
    )
    (net (code "196") (name "unconnected-(PL3-N14-Pad5)") (class "Default")
      (node (ref "PL3") (pin "5") (pinfunction "N14_5") (pintype "bidirectional"))
    )
    (net (code "197") (name "unconnected-(PL3-P8-Pad4)") (class "Default")
      (node (ref "PL3") (pin "4") (pinfunction "P8_4") (pintype "bidirectional"))
    )
    (net (code "198") (name "unconnected-(PL3-P14-Pad6)") (class "Default")
      (node (ref "PL3") (pin "6") (pinfunction "P14_6") (pintype "bidirectional"))
    )
  )
)
